# 03_ZVS_PushPull.net
KiCad netlist of a schematic drawn in Altium Designer
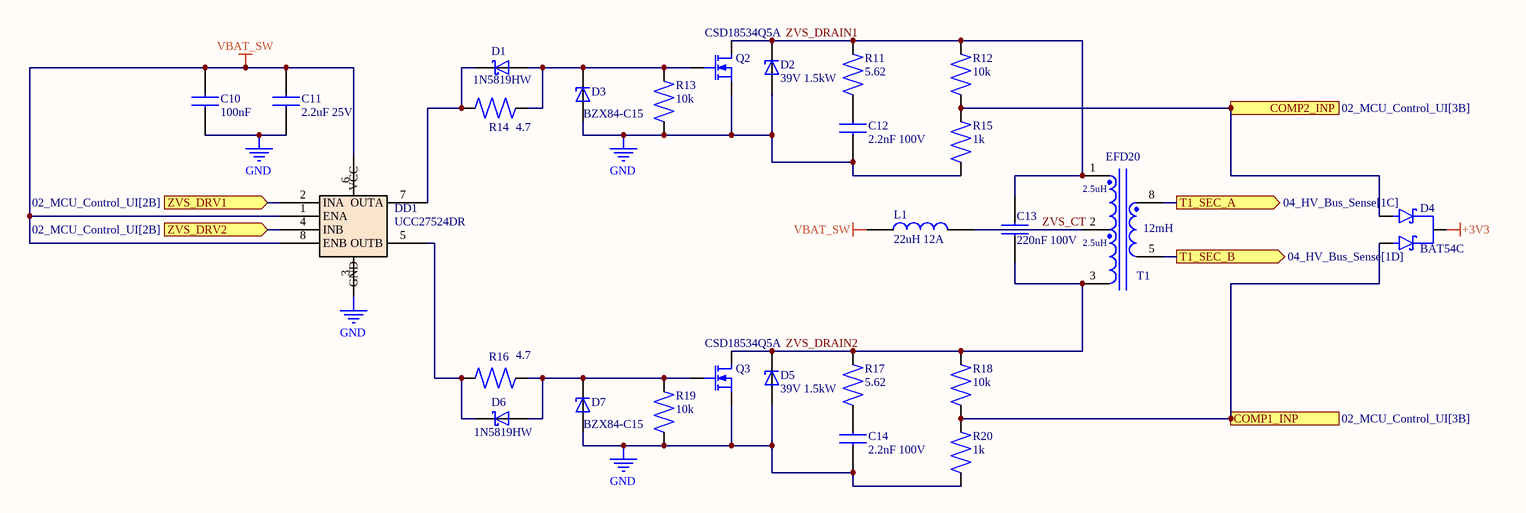
[diagram p0: 03_ZVS_PushPull.SchDoc]

(export (version "E")
  (design (tool "Eeschema 10.0.6"))
  (components
    (comp (ref "C10")
      (value "100nF")
      (footprint "CHIP_0603_SMD")
      (description "Capacitor MLCC, Ceramic, 100 nF, 50 V, ±10%, X7R, SMD 0603, Samsung Electro-Mechanics")
      (libsource (lib "Schlib1") (part "CAP_0603_100nF_50V_X7R"))
    )
    (comp (ref "C11")
      (value "2.2uF 25V")
      (footprint "CHIP_0805_SMD")
      (description "Capacitor MLCC, Ceramic, 2.2 uF, 25 V, ±10%, X7R, SMD 0805, Hitano Enterprise")
      (libsource (lib "Schlib1") (part "CAP_0805_2.2uF_25V_X7R"))
    )
    (comp (ref "C12")
      (value "2.2nF 100V")
      (footprint "CHIP_1206_SMD")
      (description "Capacitor MLCC, Ceramic, 2.2 nF, 100 V, ±5%, C0G/NP0, SMD 1206, High Frequency Snubber, Yageo")
      (libsource (lib "Schlib1") (part "CAP_1206_2.2nF_100V_C0G"))
    )
    (comp (ref "C13")
      (value "220nF 100V")
      (footprint "CAP_FILM_P15.0_CBB22_W8.5_MKP")
      (libsource (lib "Schlib1") (part "CAP_FILM_CBB22_220nF_630V_P15"))
    )
    (comp (ref "C14")
      (value "2.2nF 100V")
      (footprint "CHIP_1206_SMD")
      (description "Capacitor MLCC, Ceramic, 2.2 nF, 100 V, ±5%, C0G/NP0, SMD 1206, High Frequency Snubber, Yageo")
      (libsource (lib "Schlib1") (part "CAP_1206_2.2nF_100V_C0G"))
    )
    (comp (ref "D1")
      (value "1N5819HW")
      (footprint "SOD-123_2P_SMD")
      (description "Schottky Barrier Diode, 40V, 1A, Vf=0.45V @ 1A, SOD-123")
      (libsource (lib "Schlib1") (part "DIODE_SCHOTTKY_1N5819HW"))
    )
    (comp (ref "D2")
      (value "39V 1.5kW")
      (footprint "DIODE_DO-214AB_SMC")
      (description "TVS Diode Unidirectional, 33.3V Vwm, 1500W (10/1000us), DO-214AB (SMC), Automotive Qualified")
      (libsource (lib "Schlib1") (part "DIODE_TVS_SMC_1.5SMC39AQ"))
    )
    (comp (ref "D3")
      (value "BZX84-C15")
      (footprint "SOT-23_3P_SMD")
      (description "Zener Diode, 15V, 250mW, ±5%, SOT-23 (TO-236AB), Gate Protection, Nexperia / NXP")
      (libsource (lib "Schlib1") (part "DIODE_ZENER_BZX84-C15_SOT23"))
    )
    (comp (ref "D4")
      (value "BAT54C")
      (footprint "SOT-23_3P_SMD")
      (description "Dual Schottky Barrier Diode, Common Cathode, 30V, 200mA, Vf=0.32V @ 2mA, SOT-23")
      (libsource (lib "Schlib1") (part "DIODE_ARRAY_BAT54C_SOT23"))
    )
    (comp (ref "D5")
      (value "39V 1.5kW")
      (footprint "DIODE_DO-214AB_SMC")
      (description "TVS Diode Unidirectional, 33.3V Vwm, 1500W (10/1000us), DO-214AB (SMC), Automotive Qualified")
      (libsource (lib "Schlib1") (part "DIODE_TVS_SMC_1.5SMC39AQ"))
    )
    (comp (ref "D6")
      (value "1N5819HW")
      (footprint "SOD-123_2P_SMD")
      (description "Schottky Barrier Diode, 40V, 1A, Vf=0.45V @ 1A, SOD-123")
      (libsource (lib "Schlib1") (part "DIODE_SCHOTTKY_1N5819HW"))
    )
    (comp (ref "D7")
      (value "BZX84-C15")
      (footprint "SOT-23_3P_SMD")
      (description "Zener Diode, 15V, 250mW, ±5%, SOT-23 (TO-236AB), Gate Protection, Nexperia / NXP")
      (libsource (lib "Schlib1") (part "DIODE_ZENER_BZX84-C15_SOT23"))
    )
    (comp (ref "DD1")
      (value "UCC27524DR")
      (footprint "SOIC-8_1.27_4.9x3.9mm")
      (description "Dual 5A High-Speed Low-Side Gate Driver, 4.5V to 18V VDD, Non-Inverting, SOIC-8, Texas Instruments")
      (libsource (lib "Schlib1") (part "IC_DRIVER_UCC27524DR"))
    )
    (comp (ref "L1")
      (value "22uH 12A")
      (footprint "IND_SRP1265A_13.5x12.5_HANDSOLDER")
      (description "Inductor Power Shielded SMD, 22 uH, ±20%, 12A Irms, Ferrite Core, 13.5x12.5x6.2, SRP1265A-220M")
      (libsource (lib "Schlib1") (part "IND_SMD_22uH_12A"))
    )
    (comp (ref "Q2")
      (value "CSD18534Q5A")
      (footprint "SON-8_5x6_CSD18534Q5A_THERMAL")
      (description "MOSFET N-Channel, 60V, 69A, 3.5 mOhm, Logic Level, SON-8 (DFN 5x6), Texas Instruments")
      (libsource (lib "Schlib1") (part "MOSFET_N_60V_CSD18534Q5A"))
    )
    (comp (ref "Q3")
      (value "CSD18534Q5A")
      (footprint "SON-8_5x6_CSD18534Q5A_THERMAL")
      (description "MOSFET N-Channel, 60V, 69A, 3.5 mOhm, Logic Level, SON-8 (DFN 5x6), Texas Instruments")
      (libsource (lib "Schlib1") (part "MOSFET_N_60V_CSD18534Q5A"))
    )
    (comp (ref "R11")
      (value "5.62")
      (footprint "CHIP_1206_SMD")
      (description "Resistor, 5.62 Ohm, ±1%, 0.25W (1/4W), 200V, SMD 1206, Thick Film, Panasonic")
      (libsource (lib "Schlib1") (part "RES_1206_5.62R_1%"))
    )
    (comp (ref "R12")
      (value "10k")
      (footprint "CHIP_0603_SMD")
      (description "Resistor, 10 kOhm, ±1%, 0.1W (1/10W), 75V, SMD 0603, Thick Film, Hitano")
      (libsource (lib "Schlib1") (part "RES_0603_10k_1%"))
    )
    (comp (ref "R13")
      (value "10k")
      (footprint "CHIP_0603_SMD")
      (description "Resistor, 10 kOhm, ±1%, 0.1W (1/10W), 75V, SMD 0603, Thick Film, Hitano")
      (libsource (lib "Schlib1") (part "RES_0603_10k_1%"))
    )
    (comp (ref "R14")
      (value "4.7")
      (footprint "CHIP_0603_SMD")
      (description "Resistor, 4.7 Ohm, ±5%, 0.1W (1/10W), 50V, SMD 0603, Gate Drive Series, KOME")
      (libsource (lib "Schlib1") (part "RES_0603_4R7"))
    )
    (comp (ref "R15")
      (value "1k")
      (footprint "CHIP_0603_SMD")
      (description "Resistor, 1 kOhm, ±1%, 0.1W (1/10W), 75V, SMD 0603, Thick Film, Yageo")
      (libsource (lib "Schlib1") (part "RES_0603_1k_1%"))
    )
    (comp (ref "R16")
      (value "4.7")
      (footprint "CHIP_0603_SMD")
      (description "Resistor, 4.7 Ohm, ±5%, 0.1W (1/10W), 50V, SMD 0603, Gate Drive Series, KOME")
      (libsource (lib "Schlib1") (part "RES_0603_4R7"))
    )
    (comp (ref "R17")
      (value "5.62")
      (footprint "CHIP_1206_SMD")
      (description "Resistor, 5.62 Ohm, ±1%, 0.25W (1/4W), 200V, SMD 1206, Thick Film, Panasonic")
      (libsource (lib "Schlib1") (part "RES_1206_5.62R_1%"))
    )
    (comp (ref "R18")
      (value "10k")
      (footprint "CHIP_0603_SMD")
      (description "Resistor, 10 kOhm, ±1%, 0.1W (1/10W), 75V, SMD 0603, Thick Film, Hitano")
      (libsource (lib "Schlib1") (part "RES_0603_10k_1%"))
    )
    (comp (ref "R19")
      (value "10k")
      (footprint "CHIP_0603_SMD")
      (description "Resistor, 10 kOhm, ±1%, 0.1W (1/10W), 75V, SMD 0603, Thick Film, Hitano")
      (libsource (lib "Schlib1") (part "RES_0603_10k_1%"))
    )
    (comp (ref "R20")
      (value "1k")
      (footprint "CHIP_0603_SMD")
      (description "Resistor, 1 kOhm, ±1%, 0.1W (1/10W), 75V, SMD 0603, Thick Film, Yageo")
      (libsource (lib "Schlib1") (part "RES_0603_1k_1%"))
    )
    (comp (ref "T1")
      (value "EFD20")
      (footprint "TRANS_EFD20_CORETECH_BH-EFD20-1-8R_THT")
      (libsource (lib "Schlib1") (part "TRANS_EFD20_CUSTOM"))
    )
  )
  (nets
    (net (code "1") (name "+3V3") (class "Default")
      (node (ref "D4") (pin "3") (pinfunction "K_3") (pintype "passive"))
    )
    (net (code "2") (name "/COMP1_INP") (class "Default")
      (node (ref "D4") (pin "2") (pinfunction "A2_2") (pintype "passive"))
      (node (ref "R18") (pin "1") (pinfunction "1_1") (pintype "passive"))
      (node (ref "R20") (pin "2") (pinfunction "2_2") (pintype "passive"))
    )
    (net (code "3") (name "/COMP2_INP") (class "Default")
      (node (ref "D4") (pin "1") (pinfunction "A1_1") (pintype "passive"))
      (node (ref "R12") (pin "1") (pinfunction "1_1") (pintype "passive"))
      (node (ref "R15") (pin "2") (pinfunction "2_2") (pintype "passive"))
    )
    (net (code "4") (name "/T1_SEC_A") (class "Default")
      (node (ref "T1") (pin "8") (pinfunction "SEC1_8") (pintype "passive"))
    )
    (net (code "5") (name "/T1_SEC_B") (class "Default")
      (node (ref "T1") (pin "5") (pinfunction "SEC2_5") (pintype "passive"))
    )
    (net (code "6") (name "/ZVS_CT") (class "Default")
      (node (ref "L1") (pin "2") (pinfunction "2_2") (pintype "passive"))
      (node (ref "T1") (pin "2") (pinfunction "TAP_2") (pintype "passive"))
    )
    (net (code "7") (name "/ZVS_DRAIN1") (class "Default")
      (node (ref "C13") (pin "2") (pinfunction "2_2") (pintype "passive"))
      (node (ref "D2") (pin "1") (pinfunction "K_1") (pintype "passive"))
      (node (ref "Q2") (pin "3") (pinfunction "DR_3") (pintype "passive"))
      (node (ref "R11") (pin "2") (pinfunction "2_2") (pintype "passive"))
      (node (ref "R12") (pin "2") (pinfunction "2_2") (pintype "passive"))
      (node (ref "T1") (pin "1") (pinfunction "PRI1_1") (pintype "passive"))
    )
    (net (code "8") (name "/ZVS_DRAIN2") (class "Default")
      (node (ref "C13") (pin "1") (pinfunction "1_1") (pintype "passive"))
      (node (ref "D5") (pin "1") (pinfunction "K_1") (pintype "passive"))
      (node (ref "Q3") (pin "3") (pinfunction "DR_3") (pintype "passive"))
      (node (ref "R17") (pin "2") (pinfunction "2_2") (pintype "passive"))
      (node (ref "R18") (pin "2") (pinfunction "2_2") (pintype "passive"))
      (node (ref "T1") (pin "3") (pinfunction "PRI2_3") (pintype "passive"))
    )
    (net (code "9") (name "/ZVS_DRV1") (class "Default")
      (node (ref "DD1") (pin "2") (pinfunction "INA_2") (pintype "passive"))
    )
    (net (code "10") (name "/ZVS_DRV2") (class "Default")
      (node (ref "DD1") (pin "4") (pinfunction "INB_4") (pintype "passive"))
    )
    (net (code "11") (name "GND") (class "Default")
      (node (ref "C10") (pin "1") (pinfunction "1_1") (pintype "passive"))
      (node (ref "C11") (pin "1") (pinfunction "1_1") (pintype "passive"))
      (node (ref "C12") (pin "1") (pinfunction "1_1") (pintype "passive"))
      (node (ref "C14") (pin "1") (pinfunction "1_1") (pintype "passive"))
      (node (ref "D2") (pin "2") (pinfunction "A_2") (pintype "passive"))
      (node (ref "D3") (pin "1") (pinfunction "A_1") (pintype "passive"))
      (node (ref "D5") (pin "2") (pinfunction "A_2") (pintype "passive"))
      (node (ref "D7") (pin "1") (pinfunction "A_1") (pintype "passive"))
      (node (ref "DD1") (pin "3") (pinfunction "GND_3") (pintype "passive"))
      (node (ref "Q2") (pin "1") (pinfunction "SR_1") (pintype "passive"))
      (node (ref "Q3") (pin "1") (pinfunction "SR_1") (pintype "passive"))
      (node (ref "R13") (pin "1") (pinfunction "1_1") (pintype "passive"))
      (node (ref "R15") (pin "1") (pinfunction "1_1") (pintype "passive"))
      (node (ref "R19") (pin "1") (pinfunction "1_1") (pintype "passive"))
      (node (ref "R20") (pin "1") (pinfunction "1_1") (pintype "passive"))
    )
    (net (code "12") (name "Net-(D1-A)") (class "Default")
      (node (ref "D1") (pin "2") (pinfunction "A_2") (pintype "passive"))
      (node (ref "D3") (pin "3") (pinfunction "K_3") (pintype "passive"))
      (node (ref "Q2") (pin "2") (pinfunction "G_2") (pintype "passive"))
      (node (ref "R13") (pin "2") (pinfunction "2_2") (pintype "passive"))
      (node (ref "R14") (pin "2") (pinfunction "2_2") (pintype "passive"))
    )
    (net (code "13") (name "Net-(D1-K)") (class "Default")
      (node (ref "D1") (pin "1") (pinfunction "K_1") (pintype "passive"))
      (node (ref "DD1") (pin "7") (pinfunction "OUTA_7") (pintype "passive"))
      (node (ref "R14") (pin "1") (pinfunction "1_1") (pintype "passive"))
    )
    (net (code "14") (name "Net-(D6-A)") (class "Default")
      (node (ref "D6") (pin "2") (pinfunction "A_2") (pintype "passive"))
      (node (ref "D7") (pin "3") (pinfunction "K_3") (pintype "passive"))
      (node (ref "Q3") (pin "2") (pinfunction "G_2") (pintype "passive"))
      (node (ref "R16") (pin "2") (pinfunction "2_2") (pintype "passive"))
      (node (ref "R19") (pin "2") (pinfunction "2_2") (pintype "passive"))
    )
    (net (code "15") (name "Net-(D6-K)") (class "Default")
      (node (ref "D6") (pin "1") (pinfunction "K_1") (pintype "passive"))
      (node (ref "DD1") (pin "5") (pinfunction "OUTB_5") (pintype "passive"))
      (node (ref "R16") (pin "1") (pinfunction "1_1") (pintype "passive"))
    )
    (net (code "16") (name "VBAT_SW") (class "Default")
      (node (ref "C10") (pin "2") (pinfunction "2_2") (pintype "passive"))
      (node (ref "C11") (pin "2") (pinfunction "2_2") (pintype "passive"))
      (node (ref "DD1") (pin "1") (pinfunction "ENA_1") (pintype "passive"))
      (node (ref "DD1") (pin "6") (pinfunction "VCC_6") (pintype "passive"))
      (node (ref "DD1") (pin "8") (pinfunction "ENB_8") (pintype "passive"))
      (node (ref "L1") (pin "1") (pinfunction "1_1") (pintype "passive"))
    )
    (net (code "17") (name "unconnected-(C12-Pad2)") (class "Default")
      (node (ref "C12") (pin "2") (pinfunction "2_2") (pintype "passive"))
    )
    (net (code "18") (name "unconnected-(C14-Pad2)") (class "Default")
      (node (ref "C14") (pin "2") (pinfunction "2_2") (pintype "passive"))
    )
    (net (code "19") (name "unconnected-(R11-Pad1)") (class "Default")
      (node (ref "R11") (pin "1") (pinfunction "1_1") (pintype "passive"))
    )
    (net (code "20") (name "unconnected-(R17-Pad1)") (class "Default")
      (node (ref "R17") (pin "1") (pinfunction "1_1") (pintype "passive"))
    )
  )
)
